# breakout.net
KiCad netlist of a schematic drawn in EAGLE
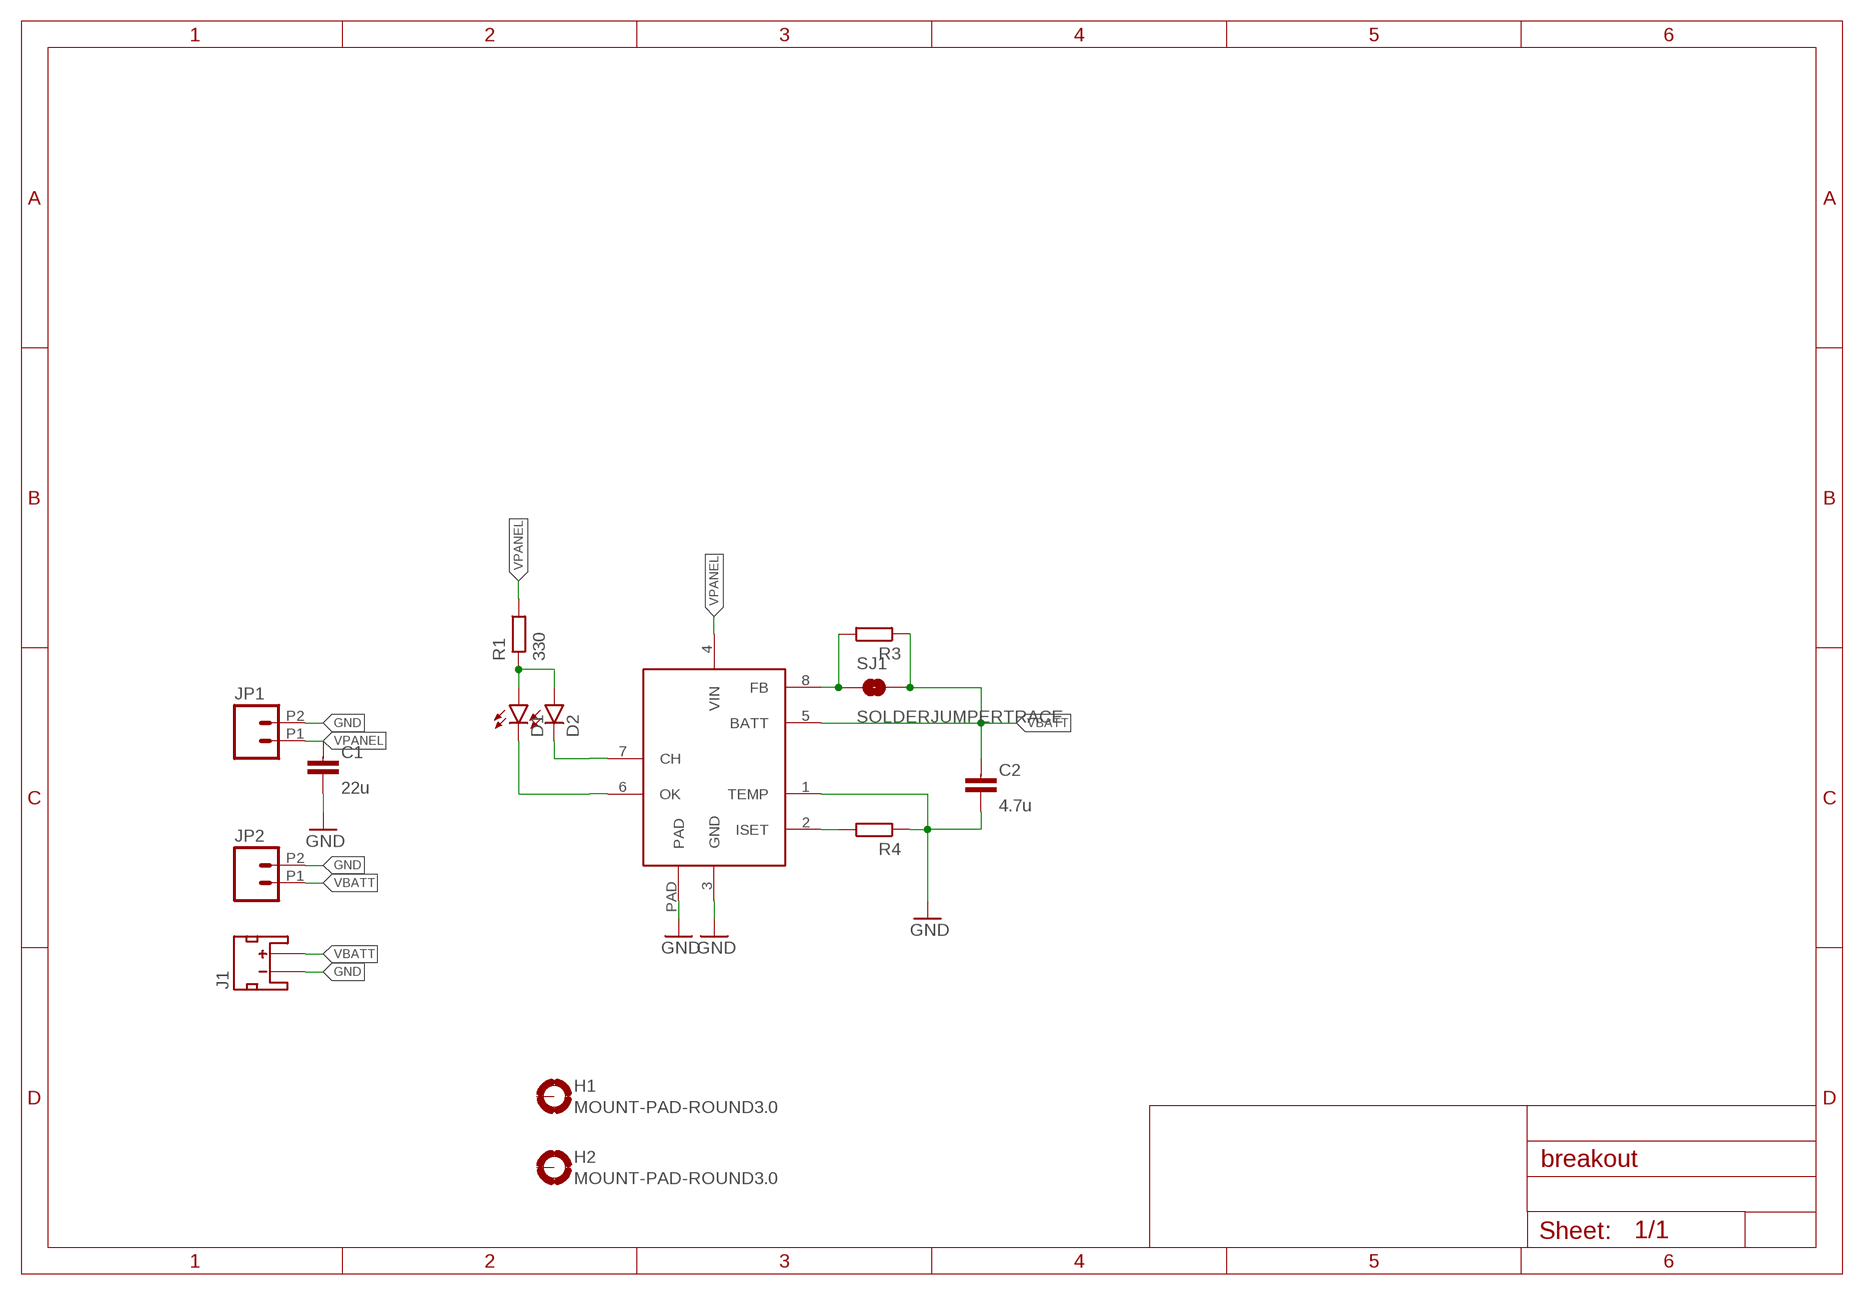
[diagram p0: schematic, sheet 1]

(export (version "E")
  (design (tool "Eeschema 10.0.6"))
  (components
    (comp (ref "C1")
      (value "22u")
      (footprint "eagle-import:C0603-N")
      (libsource (lib "eagle-import") (part "CAPACITOR0603-N"))
    )
    (comp (ref "C2")
      (value "4.7u")
      (footprint "eagle-import:C0603-N")
      (libsource (lib "eagle-import") (part "CAPACITOR0603-N"))
    )
    (comp (ref "D1")
      (value "LED0603")
      (footprint "eagle-import:LED-0603")
      (libsource (lib "eagle-import") (part "LED0603"))
    )
    (comp (ref "D2")
      (value "LED0603")
      (footprint "eagle-import:LED-0603")
      (libsource (lib "eagle-import") (part "LED0603"))
    )
    (comp (ref "H1")
      (value "MOUNT-PAD-ROUND3.0")
      (footprint "eagle-import:3,0-PAD")
      (libsource (lib "eagle-import") (part "MOUNT-PAD-ROUND3.0"))
    )
    (comp (ref "H2")
      (value "MOUNT-PAD-ROUND3.0")
      (footprint "eagle-import:3,0-PAD")
      (libsource (lib "eagle-import") (part "MOUNT-PAD-ROUND3.0"))
    )
    (comp (ref "J1")
      (value "JST_2MM_MALE_TH")
      (footprint "eagle-import:JST-2-TH")
      (libsource (lib "eagle-import") (part "JST_2MM_MALE_TH"))
    )
    (comp (ref "JP1")
      (value "M022.54MM_SCREWTERM")
      (footprint "eagle-import:1X02_2.54_SCREWTERM")
      (libsource (lib "eagle-import") (part "M022.54MM_SCREWTERM"))
    )
    (comp (ref "JP2")
      (value "M022.54MM_SCREWTERM")
      (footprint "eagle-import:1X02_2.54_SCREWTERM")
      (libsource (lib "eagle-import") (part "M022.54MM_SCREWTERM"))
    )
    (comp (ref "R1")
      (value "330")
      (footprint "eagle-import:R0603-N")
      (libsource (lib "eagle-import") (part "RESISTOR0603-N"))
    )
    (comp (ref "R3")
      (value "RESISTOR0603-N")
      (footprint "eagle-import:R0603-N")
      (libsource (lib "eagle-import") (part "RESISTOR0603-N"))
    )
    (comp (ref "R4")
      (value "RESISTOR0603-N")
      (footprint "eagle-import:R0603-N")
      (libsource (lib "eagle-import") (part "RESISTOR0603-N"))
    )
    (comp (ref "SJ1")
      (value "SOLDERJUMPERTRACE")
      (footprint "eagle-import:SJ_2S-TRACE")
      (libsource (lib "eagle-import") (part "SOLDERJUMPERTRACE"))
    )
    (comp (ref "U1")
      (value "CN3083")
      (footprint "eagle-import:SO8-PAD")
      (libsource (lib "eagle-import") (part "CN3083"))
    )
  )
  (nets
    (net (code "1") (name "GND") (class "Default")
      (node (ref "C1") (pin "2") (pinfunction "2_2") (pintype "passive"))
      (node (ref "C2") (pin "2") (pinfunction "2_2") (pintype "passive"))
      (node (ref "J1") (pin "2") (pinfunction "-_2") (pintype "bidirectional"))
      (node (ref "JP1") (pin "P2") (pinfunction "2_P2") (pintype "passive"))
      (node (ref "JP2") (pin "P2") (pinfunction "2_P2") (pintype "passive"))
      (node (ref "R4") (pin "1") (pinfunction "P$1_1") (pintype "passive"))
      (node (ref "U1") (pin "1") (pinfunction "TEMP_1") (pintype "bidirectional"))
      (node (ref "U1") (pin "3") (pinfunction "GND_3") (pintype "bidirectional"))
      (node (ref "U1") (pin "PAD") (pinfunction "PAD_PAD") (pintype "bidirectional"))
    )
    (net (code "2") (name "Net-(R1-P$1)") (class "Default")
      (node (ref "D1") (pin "A") (pinfunction "A_A") (pintype "passive"))
      (node (ref "D2") (pin "A") (pinfunction "A_A") (pintype "passive"))
      (node (ref "R1") (pin "1") (pinfunction "P$1_1") (pintype "passive"))
    )
    (net (code "3") (name "Net-(R3-P$2)") (class "Default")
      (node (ref "R3") (pin "2") (pinfunction "P$2_2") (pintype "passive"))
      (node (ref "SJ1") (pin "1") (pinfunction "1_1") (pintype "passive"))
      (node (ref "U1") (pin "8") (pinfunction "FB_8") (pintype "bidirectional"))
    )
    (net (code "4") (name "Net-(R4-P$2)") (class "Default")
      (node (ref "R4") (pin "2") (pinfunction "P$2_2") (pintype "passive"))
      (node (ref "U1") (pin "2") (pinfunction "ISET_2") (pintype "bidirectional"))
    )
    (net (code "5") (name "Net-(U1-CH)") (class "Default")
      (node (ref "D2") (pin "C") (pinfunction "C_C") (pintype "passive"))
      (node (ref "U1") (pin "7") (pinfunction "CH_7") (pintype "bidirectional"))
    )
    (net (code "6") (name "Net-(U1-OK)") (class "Default")
      (node (ref "D1") (pin "C") (pinfunction "C_C") (pintype "passive"))
      (node (ref "U1") (pin "6") (pinfunction "OK_6") (pintype "bidirectional"))
    )
    (net (code "7") (name "VBATT") (class "Default")
      (node (ref "C2") (pin "1") (pinfunction "1_1") (pintype "passive"))
      (node (ref "J1") (pin "1") (pinfunction "+_1") (pintype "bidirectional"))
      (node (ref "JP2") (pin "P1") (pinfunction "1_P1") (pintype "passive"))
      (node (ref "R3") (pin "1") (pinfunction "P$1_1") (pintype "passive"))
      (node (ref "SJ1") (pin "2") (pinfunction "2_2") (pintype "passive"))
      (node (ref "U1") (pin "5") (pinfunction "BATT_5") (pintype "bidirectional"))
    )
    (net (code "8") (name "VPANEL") (class "Default")
      (node (ref "C1") (pin "1") (pinfunction "1_1") (pintype "passive"))
      (node (ref "JP1") (pin "P1") (pinfunction "1_P1") (pintype "passive"))
      (node (ref "R1") (pin "2") (pinfunction "P$2_2") (pintype "passive"))
      (node (ref "U1") (pin "4") (pinfunction "VIN_4") (pintype "bidirectional"))
    )
    (net (code "9") (name "unconnected-(H1-MOUNT-PadB3,0)") (class "Default")
      (node (ref "H1") (pin "B3,0") (pinfunction "MOUNT_B3,0") (pintype "passive"))
    )
    (net (code "10") (name "unconnected-(H2-MOUNT-PadB3,0)") (class "Default")
      (node (ref "H2") (pin "B3,0") (pinfunction "MOUNT_B3,0") (pintype "passive"))
    )
  )
)
